# arduino_helper.net
KiCad netlist of a schematic drawn in EAGLE
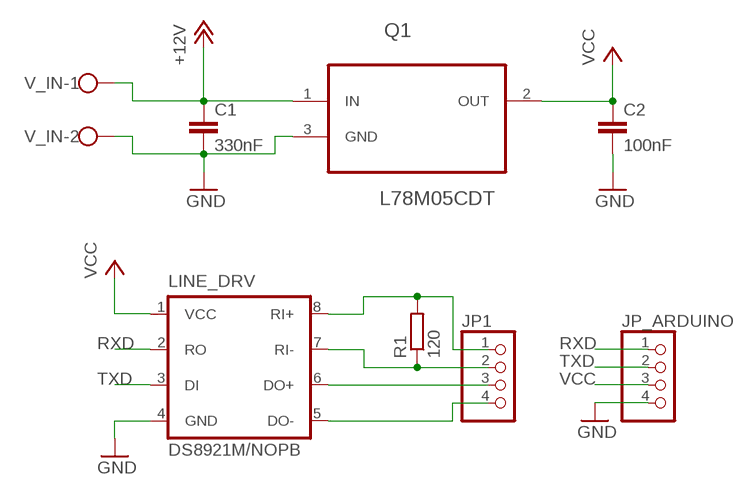
[diagram p0: schematic, sheet 1]

(export (version "E")
  (design (tool "Eeschema 10.0.6"))
  (components
    (comp (ref "C1")
      (value "330nF")
      (footprint "eagle-import:C0805")
      (libsource (lib "eagle-import") (part "C-EUC0805"))
    )
    (comp (ref "C2")
      (value "100nF")
      (footprint "eagle-import:C0805")
      (libsource (lib "eagle-import") (part "C-EUC0805"))
    )
    (comp (ref "JP1")
      (value "PINHD-1X4")
      (footprint "eagle-import:1X04")
      (libsource (lib "eagle-import") (part "PINHD-1X4"))
    )
    (comp (ref "JP_ARDUINO")
      (value "PINHD-1X4")
      (footprint "eagle-import:1X04")
      (libsource (lib "eagle-import") (part "PINHD-1X4"))
    )
    (comp (ref "LINE_DRV")
      (value "DS8921M/NOPB")
      (footprint "eagle-import:SOIC8")
      (libsource (lib "eagle-import") (part "DS8921M/NOPB"))
    )
    (comp (ref "Q1")
      (value "L78M05CDT")
      (footprint "eagle-import:TO225P972X240-3N")
      (libsource (lib "eagle-import") (part "L78M05CDT"))
    )
    (comp (ref "R1")
      (value "120")
      (footprint "eagle-import:R0805")
      (libsource (lib "eagle-import") (part "R-EU_R0805"))
    )
    (comp (ref "V_IN")
      (value "W237-102")
      (footprint "eagle-import:W237-102")
      (fields (field (name "MPN") "237-102"))
      (libsource (lib "eagle-import") (part "W237-102"))
    )
  )
  (nets
    (net (code "1") (name "+12V") (class "Default")
      (node (ref "C1") (pin "1") (pinfunction "1_1") (pintype "passive"))
      (node (ref "Q1") (pin "1") (pinfunction "IN_1") (pintype "input"))
      (node (ref "V_IN") (pin "1") (pinfunction "KL_1") (pintype "passive"))
    )
    (net (code "2") (name "/RXD") (class "Default")
      (node (ref "JP_ARDUINO") (pin "1") (pinfunction "1_1") (pintype "passive"))
      (node (ref "LINE_DRV") (pin "2") (pinfunction "RO_2") (pintype "output"))
    )
    (net (code "3") (name "/TXD") (class "Default")
      (node (ref "JP_ARDUINO") (pin "2") (pinfunction "2_2") (pintype "passive"))
      (node (ref "LINE_DRV") (pin "3") (pinfunction "DI_3") (pintype "input"))
    )
    (net (code "4") (name "GND") (class "Default")
      (node (ref "C1") (pin "2") (pinfunction "2_2") (pintype "passive"))
      (node (ref "C2") (pin "2") (pinfunction "2_2") (pintype "passive"))
      (node (ref "JP_ARDUINO") (pin "4") (pinfunction "4_4") (pintype "passive"))
      (node (ref "LINE_DRV") (pin "4") (pinfunction "GND_4") (pintype "power_in"))
      (node (ref "Q1") (pin "3") (pinfunction "GND_3") (pintype "passive"))
      (node (ref "V_IN") (pin "2") (pinfunction "KL_2") (pintype "passive"))
    )
    (net (code "5") (name "Net-(LINE_DRV-DO+)") (class "Default")
      (node (ref "JP1") (pin "3") (pinfunction "3_3") (pintype "passive"))
      (node (ref "LINE_DRV") (pin "6") (pinfunction "DO+_6") (pintype "output"))
    )
    (net (code "6") (name "Net-(LINE_DRV-DO-)") (class "Default")
      (node (ref "JP1") (pin "4") (pinfunction "4_4") (pintype "passive"))
      (node (ref "LINE_DRV") (pin "5") (pinfunction "DO-_5") (pintype "output"))
    )
    (net (code "7") (name "Net-(LINE_DRV-RI+)") (class "Default")
      (node (ref "JP1") (pin "1") (pinfunction "1_1") (pintype "passive"))
      (node (ref "LINE_DRV") (pin "8") (pinfunction "RI+_8") (pintype "input"))
      (node (ref "R1") (pin "2") (pinfunction "2_2") (pintype "passive"))
    )
    (net (code "8") (name "Net-(LINE_DRV-RI-)") (class "Default")
      (node (ref "JP1") (pin "2") (pinfunction "2_2") (pintype "passive"))
      (node (ref "LINE_DRV") (pin "7") (pinfunction "RI-_7") (pintype "input"))
      (node (ref "R1") (pin "1") (pinfunction "1_1") (pintype "passive"))
    )
    (net (code "9") (name "VCC") (class "Default")
      (node (ref "C2") (pin "1") (pinfunction "1_1") (pintype "passive"))
      (node (ref "JP_ARDUINO") (pin "3") (pinfunction "3_3") (pintype "passive"))
      (node (ref "LINE_DRV") (pin "1") (pinfunction "VCC_1") (pintype "power_in"))
      (node (ref "Q1") (pin "2") (pinfunction "OUT_2") (pintype "output"))
    )
  )
)
